# Detector_Ausencia_Luz.net
KiCad netlist of a schematic drawn in EAGLE
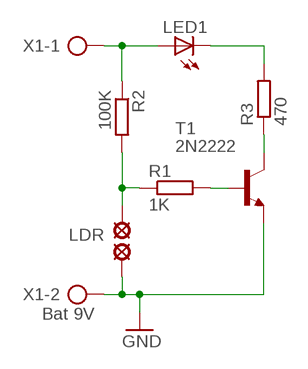
[diagram p0: schematic, sheet 1]

(export (version "E")
  (design (tool "Eeschema 10.0.6"))
  (components
    (comp (ref "LED1")
      (value "LED5MM")
      (footprint "eagle-import:LED5MM")
      (libsource (lib "eagle-import") (part "LED5MM"))
    )
    (comp (ref "LSP1")
      (value "SE11")
      (footprint "eagle-import:SE11")
      (libsource (lib "eagle-import") (part "SE11"))
    )
    (comp (ref "LSP2")
      (value "SE11")
      (footprint "eagle-import:SE11")
      (libsource (lib "eagle-import") (part "SE11"))
    )
    (comp (ref "R1")
      (value "1K")
      (footprint "eagle-import:0207_10")
      (libsource (lib "eagle-import") (part "R-EU_0207/10"))
    )
    (comp (ref "R2")
      (value "100K")
      (footprint "eagle-import:0207_10")
      (libsource (lib "eagle-import") (part "R-EU_0207/10"))
    )
    (comp (ref "R3")
      (value "470")
      (footprint "eagle-import:0207_10")
      (libsource (lib "eagle-import") (part "R-EU_0207/10"))
    )
    (comp (ref "T1")
      (value "2N2222")
      (footprint "eagle-import:TO92-CBE")
      (libsource (lib "eagle-import") (part "-NPN-TO92-CBEMPS2222A"))
    )
    (comp (ref "X1")
      (value "Bat 9V")
      (footprint "eagle-import:AK500_2")
      (libsource (lib "eagle-import") (part "AK500/2"))
    )
  )
  (nets
    (net (code "1") (name "GND") (class "Default")
      (node (ref "LSP2") (pin "MP") (pinfunction "MP_MP") (pintype "passive"))
      (node (ref "T1") (pin "E") (pinfunction "E_E") (pintype "passive"))
      (node (ref "X1") (pin "2") (pinfunction "KL_2") (pintype "passive"))
    )
    (net (code "2") (name "Net-(LED1-C)") (class "Default")
      (node (ref "LED1") (pin "K") (pinfunction "C_K") (pintype "passive"))
      (node (ref "R3") (pin "2") (pinfunction "2_2") (pintype "passive"))
    )
    (net (code "3") (name "Net-(LSP1-PadMP)") (class "Default")
      (node (ref "LSP1") (pin "MP") (pinfunction "MP_MP") (pintype "passive"))
      (node (ref "R1") (pin "1") (pinfunction "1_1") (pintype "passive"))
      (node (ref "R2") (pin "2") (pinfunction "2_2") (pintype "passive"))
    )
    (net (code "4") (name "Net-(R1-Pad2)") (class "Default")
      (node (ref "R1") (pin "2") (pinfunction "2_2") (pintype "passive"))
      (node (ref "T1") (pin "B") (pinfunction "B_B") (pintype "passive"))
    )
    (net (code "5") (name "Net-(R3-Pad1)") (class "Default")
      (node (ref "R3") (pin "1") (pinfunction "1_1") (pintype "passive"))
      (node (ref "T1") (pin "C") (pinfunction "C_C") (pintype "passive"))
    )
    (net (code "6") (name "Net-(X1A-KL)") (class "Default")
      (node (ref "LED1") (pin "A") (pinfunction "A_A") (pintype "passive"))
      (node (ref "R2") (pin "1") (pinfunction "1_1") (pintype "passive"))
      (node (ref "X1") (pin "1") (pinfunction "KL_1") (pintype "passive"))
    )
  )
)
